# 2s_HY2120-OB.net
KiCad netlist of a schematic drawn in EasyEDA Pro
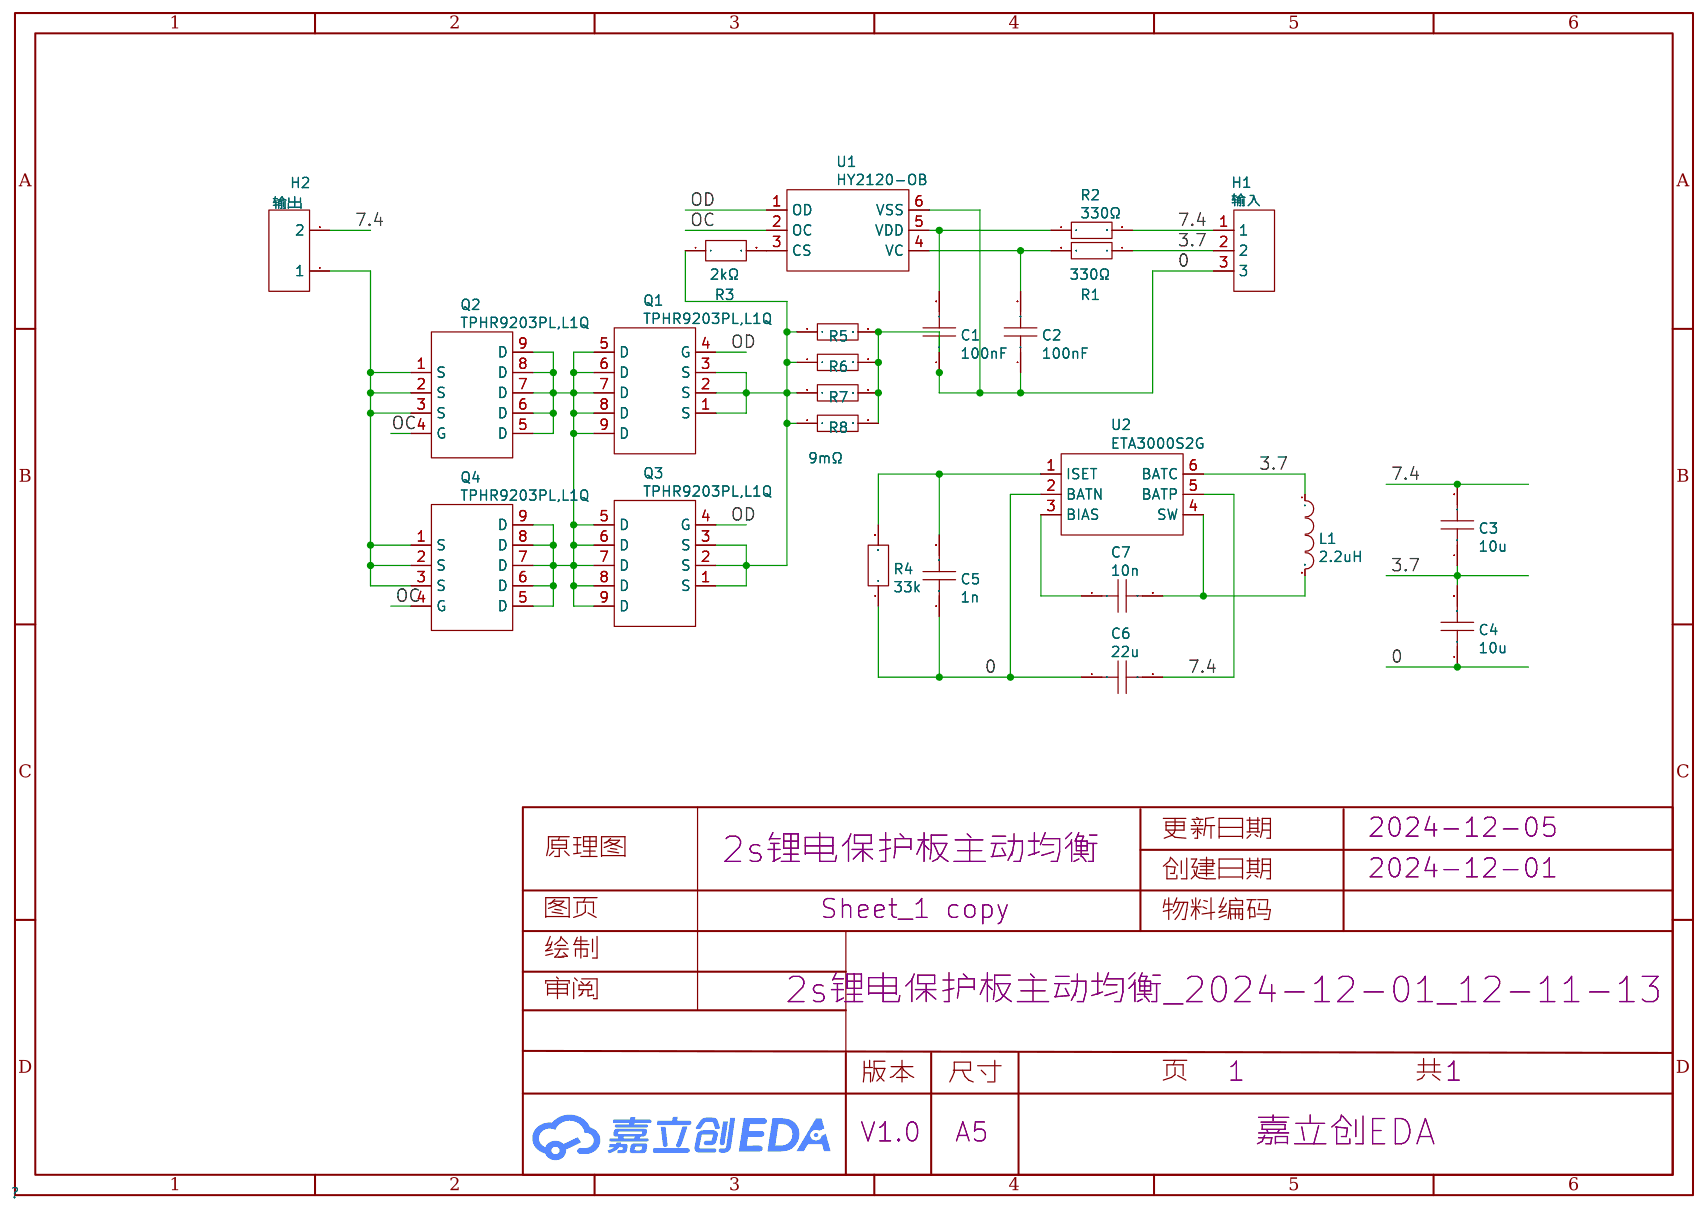
[diagram p0: schematic sheet]

(export (version "E")
  (design (tool "Eeschema 10.0.6"))
  (components
    (comp (ref "C1")
      (value "100nF")
      (footprint "easyedapro:C0603")
      (fields (field (name "Manufacturer Part") "CL10B104KC8NNNC") (field (name "Manufacturer") "SAMSUNG"))
      (libsource (lib "easyedapro") (part "100nF"))
    )
    (comp (ref "C2")
      (value "100nF")
      (footprint "easyedapro:C0603")
      (fields (field (name "Manufacturer Part") "CL10B104KC8NNNC") (field (name "Manufacturer") "SAMSUNG"))
      (libsource (lib "easyedapro") (part "100nF"))
    )
    (comp (ref "C3") (value "10u") (footprint "easyedapro:C0603") (libsource (lib "easyedapro") (part "10u")))
    (comp (ref "C4") (value "10u") (footprint "easyedapro:C0603") (libsource (lib "easyedapro") (part "10u")))
    (comp (ref "C5") (value "1n") (footprint "easyedapro:C0603") (libsource (lib "easyedapro") (part "1n")))
    (comp (ref "C6") (value "22u") (footprint "easyedapro:C0603") (libsource (lib "easyedapro") (part "22u")))
    (comp (ref "C7") (value "10n") (footprint "easyedapro:C0603") (libsource (lib "easyedapro") (part "10n")))
    (comp (ref "H1")
      (value "输入")
      (fields
        (field (name "Manufacturer Part") "Z-211-0311-0021-001")
        (field (name "Manufacturer") "ZHENGLING")
      )
      (libsource (lib "easyedapro") (part "输入"))
    )
    (comp (ref "H2")
      (value "输出")
      (fields (field (name "Manufacturer Part") "826629-2") (field (name "Manufacturer") "TE Connectivity"))
      (libsource (lib "easyedapro") (part "输出"))
    )
    (comp (ref "L1")
      (value "2.2uH")
      (footprint "easyedapro:IND-SMD_L4.4-W4.0_PHC0420")
      (fields (field (name "Manufacturer Part") "PHC0420-2R2M-T") (field (name "Manufacturer") "EMTEK"))
      (libsource (lib "easyedapro") (part "2.2uH"))
    )
    (comp (ref "Q1")
      (value "TPHR9203PL,L1Q")
      (footprint "easyedapro:DSOP-8_L5.0-W5.0-P1.27-EP-TL")
      (fields (field (name "Manufacturer") "TOSHIBA(东芝)"))
      (libsource (lib "easyedapro") (part "TPH1R403NL"))
    )
    (comp (ref "Q2")
      (value "TPHR9203PL,L1Q")
      (footprint "easyedapro:DSOP-8_L5.0-W5.0-P1.27-EP-TL")
      (fields (field (name "Manufacturer") "TOSHIBA(东芝)"))
      (libsource (lib "easyedapro") (part "TPH1R403NL"))
    )
    (comp (ref "Q3")
      (value "TPHR9203PL,L1Q")
      (footprint "easyedapro:DSOP-8_L5.0-W5.0-P1.27-EP-TL")
      (fields (field (name "Manufacturer") "TOSHIBA(东芝)"))
      (libsource (lib "easyedapro") (part "TPH1R403NL"))
    )
    (comp (ref "Q4")
      (value "TPHR9203PL,L1Q")
      (footprint "easyedapro:DSOP-8_L5.0-W5.0-P1.27-EP-TL")
      (fields (field (name "Manufacturer") "TOSHIBA(东芝)"))
      (libsource (lib "easyedapro") (part "TPH1R403NL"))
    )
    (comp (ref "R1")
      (value "330Ω")
      (footprint "easyedapro:R0603")
      (fields
        (field (name "Manufacturer Part") "RN731JTTD3300B25")
        (field (name "Manufacturer") "KOA Speer Elec")
      )
      (libsource (lib "easyedapro") (part "330Ω"))
    )
    (comp (ref "R2")
      (value "330Ω")
      (footprint "easyedapro:R0603")
      (fields
        (field (name "Manufacturer Part") "RN731JTTD3300B25")
        (field (name "Manufacturer") "KOA Speer Elec")
      )
      (libsource (lib "easyedapro") (part "330Ω"))
    )
    (comp (ref "R3")
      (value "2kΩ")
      (footprint "easyedapro:R0603")
      (fields
        (field (name "Manufacturer Part") "0603WAD2001T5E")
        (field (name "Manufacturer") "Uniroyal Elec")
      )
      (libsource (lib "easyedapro") (part "2kΩ"))
    )
    (comp (ref "R4") (value "33k") (footprint "easyedapro:R0603") (libsource (lib "easyedapro") (part "33k")))
    (comp (ref "R5")
      (value "9mΩ")
      (footprint "easyedapro:R1206")
      (description "阻值:9mΩ;精度:±1%;功率:1W;温度系数:±100ppm/°C;")
      (fields
        (field (name "Manufacturer Part") "STE1206M1W0R009F")
        (field (name "Manufacturer") "WALTER(华德)")
      )
      (libsource (lib "easyedapro") (part "STE1206M1W0R009F"))
    )
    (comp (ref "R6")
      (value "9mΩ")
      (footprint "easyedapro:R1206")
      (description "阻值:9mΩ;精度:±1%;功率:1W;温度系数:±100ppm/°C;")
      (fields
        (field (name "Manufacturer Part") "STE1206M1W0R009F")
        (field (name "Manufacturer") "WALTER(华德)")
      )
      (libsource (lib "easyedapro") (part "STE1206M1W0R009F"))
    )
    (comp (ref "R7")
      (value "9mΩ")
      (footprint "easyedapro:R1206")
      (description "阻值:9mΩ;精度:±1%;功率:1W;温度系数:±100ppm/°C;")
      (fields
        (field (name "Manufacturer Part") "STE1206M1W0R009F")
        (field (name "Manufacturer") "WALTER(华德)")
      )
      (libsource (lib "easyedapro") (part "STE1206M1W0R009F"))
    )
    (comp (ref "R8")
      (value "9mΩ")
      (footprint "easyedapro:R1206")
      (description "阻值:9mΩ;精度:±1%;功率:1W;温度系数:±100ppm/°C;")
      (fields
        (field (name "Manufacturer Part") "STE1206M1W0R009F")
        (field (name "Manufacturer") "WALTER(华德)")
      )
      (libsource (lib "easyedapro") (part "STE1206M1W0R009F"))
    )
    (comp (ref "U1")
      (value "HY2120-OB")
      (footprint "easyedapro:SOT-23-6_L2.9-W1.6-P0.95-LS2.8-BR")
      (fields (field (name "Manufacturer Part") "HY2120-LB") (field (name "Manufacturer") "HYCON"))
      (libsource (lib "easyedapro") (part "HY2120-OB"))
    )
    (comp (ref "U2")
      (value "ETA3000S2G")
      (footprint "easyedapro:SOT-23-6_L2.9-W1.6-P0.95-LS2.8-BL")
      (fields (field (name "Manufacturer") "ETA(钰泰)"))
      (libsource (lib "easyedapro") (part "ETA3000S2G"))
    )
  )
  (nets
    (net (code "1") (name "/0") (class "Default")
      (node (ref "C1") (pin "1") (pinfunction "1_1") (pintype "unspecified"))
      (node (ref "C2") (pin "1") (pinfunction "1_1") (pintype "unspecified"))
      (node (ref "C4") (pin "1") (pinfunction "1_1") (pintype "unspecified"))
      (node (ref "C5") (pin "1") (pinfunction "1_1") (pintype "unspecified"))
      (node (ref "C6") (pin "1") (pinfunction "1_1") (pintype "unspecified"))
      (node (ref "H1") (pin "3") (pinfunction "3_3") (pintype "unspecified"))
      (node (ref "R4") (pin "1") (pinfunction "1_1") (pintype "unspecified"))
      (node (ref "R5") (pin "2") (pinfunction "2_2") (pintype "unspecified"))
      (node (ref "R6") (pin "2") (pinfunction "2_2") (pintype "unspecified"))
      (node (ref "R7") (pin "2") (pinfunction "2_2") (pintype "unspecified"))
      (node (ref "R8") (pin "2") (pinfunction "2_2") (pintype "unspecified"))
      (node (ref "U1") (pin "6") (pinfunction "VSS_6") (pintype "unspecified"))
      (node (ref "U2") (pin "2") (pinfunction "BATN_2") (pintype "unspecified"))
    )
    (net (code "2") (name "/3.7") (class "Default")
      (node (ref "C3") (pin "1") (pinfunction "1_1") (pintype "unspecified"))
      (node (ref "C4") (pin "2") (pinfunction "2_2") (pintype "unspecified"))
      (node (ref "H1") (pin "2") (pinfunction "2_2") (pintype "unspecified"))
      (node (ref "L1") (pin "1") (pinfunction "1_1") (pintype "unspecified"))
      (node (ref "R1") (pin "1") (pinfunction "1_1") (pintype "unspecified"))
      (node (ref "U2") (pin "6") (pinfunction "BATC_6") (pintype "unspecified"))
    )
    (net (code "3") (name "/7.4") (class "Default")
      (node (ref "C3") (pin "2") (pinfunction "2_2") (pintype "unspecified"))
      (node (ref "C6") (pin "2") (pinfunction "2_2") (pintype "unspecified"))
      (node (ref "H1") (pin "1") (pinfunction "1_1") (pintype "unspecified"))
      (node (ref "H2") (pin "2") (pinfunction "2_2") (pintype "unspecified"))
      (node (ref "R2") (pin "2") (pinfunction "2_2") (pintype "unspecified"))
      (node (ref "U2") (pin "5") (pinfunction "BATP_5") (pintype "unspecified"))
    )
    (net (code "4") (name "/OC") (class "Default")
      (node (ref "Q2") (pin "4") (pinfunction "G_4") (pintype "unspecified"))
      (node (ref "Q4") (pin "4") (pinfunction "G_4") (pintype "unspecified"))
      (node (ref "U1") (pin "2") (pinfunction "OC_2") (pintype "unspecified"))
    )
    (net (code "5") (name "/OD") (class "Default")
      (node (ref "Q1") (pin "4") (pinfunction "G_4") (pintype "unspecified"))
      (node (ref "Q3") (pin "4") (pinfunction "G_4") (pintype "unspecified"))
      (node (ref "U1") (pin "1") (pinfunction "OD_1") (pintype "unspecified"))
    )
    (net (code "6") (name "Net-(H2-Pad1)") (class "Default")
      (node (ref "H2") (pin "1") (pinfunction "1_1") (pintype "unspecified"))
      (node (ref "Q2") (pin "1") (pinfunction "S_1") (pintype "unspecified"))
      (node (ref "Q2") (pin "2") (pinfunction "S_2") (pintype "unspecified"))
      (node (ref "Q2") (pin "3") (pinfunction "S_3") (pintype "unspecified"))
      (node (ref "Q4") (pin "1") (pinfunction "S_1") (pintype "unspecified"))
      (node (ref "Q4") (pin "2") (pinfunction "S_2") (pintype "unspecified"))
      (node (ref "Q4") (pin "3") (pinfunction "S_3") (pintype "unspecified"))
    )
    (net (code "7") (name "Net-(Q1-D-Pad5)") (class "Default")
      (node (ref "Q1") (pin "5") (pinfunction "D_5") (pintype "unspecified"))
      (node (ref "Q1") (pin "6") (pinfunction "D_6") (pintype "unspecified"))
      (node (ref "Q1") (pin "7") (pinfunction "D_7") (pintype "unspecified"))
      (node (ref "Q1") (pin "8") (pinfunction "D_8") (pintype "unspecified"))
      (node (ref "Q1") (pin "9") (pinfunction "D_9") (pintype "unspecified"))
      (node (ref "Q2") (pin "5") (pinfunction "D_5") (pintype "unspecified"))
      (node (ref "Q2") (pin "6") (pinfunction "D_6") (pintype "unspecified"))
      (node (ref "Q2") (pin "7") (pinfunction "D_7") (pintype "unspecified"))
      (node (ref "Q2") (pin "8") (pinfunction "D_8") (pintype "unspecified"))
      (node (ref "Q2") (pin "9") (pinfunction "D_9") (pintype "unspecified"))
      (node (ref "Q3") (pin "5") (pinfunction "D_5") (pintype "unspecified"))
      (node (ref "Q3") (pin "6") (pinfunction "D_6") (pintype "unspecified"))
      (node (ref "Q3") (pin "7") (pinfunction "D_7") (pintype "unspecified"))
      (node (ref "Q3") (pin "8") (pinfunction "D_8") (pintype "unspecified"))
      (node (ref "Q3") (pin "9") (pinfunction "D_9") (pintype "unspecified"))
      (node (ref "Q4") (pin "5") (pinfunction "D_5") (pintype "unspecified"))
      (node (ref "Q4") (pin "6") (pinfunction "D_6") (pintype "unspecified"))
      (node (ref "Q4") (pin "7") (pinfunction "D_7") (pintype "unspecified"))
      (node (ref "Q4") (pin "8") (pinfunction "D_8") (pintype "unspecified"))
      (node (ref "Q4") (pin "9") (pinfunction "D_9") (pintype "unspecified"))
    )
    (net (code "8") (name "Net-(Q1-S-Pad1)") (class "Default")
      (node (ref "Q1") (pin "1") (pinfunction "S_1") (pintype "unspecified"))
      (node (ref "Q1") (pin "2") (pinfunction "S_2") (pintype "unspecified"))
      (node (ref "Q1") (pin "3") (pinfunction "S_3") (pintype "unspecified"))
      (node (ref "Q3") (pin "1") (pinfunction "S_1") (pintype "unspecified"))
      (node (ref "Q3") (pin "2") (pinfunction "S_2") (pintype "unspecified"))
      (node (ref "Q3") (pin "3") (pinfunction "S_3") (pintype "unspecified"))
      (node (ref "R3") (pin "1") (pinfunction "1_1") (pintype "unspecified"))
      (node (ref "R5") (pin "1") (pinfunction "1_1") (pintype "unspecified"))
      (node (ref "R6") (pin "1") (pinfunction "1_1") (pintype "unspecified"))
      (node (ref "R7") (pin "1") (pinfunction "1_1") (pintype "unspecified"))
      (node (ref "R8") (pin "1") (pinfunction "1_1") (pintype "unspecified"))
    )
    (net (code "9") (name "Net-(U1-CS)") (class "Default")
      (node (ref "R3") (pin "2") (pinfunction "2_2") (pintype "unspecified"))
      (node (ref "U1") (pin "3") (pinfunction "CS_3") (pintype "unspecified"))
    )
    (net (code "10") (name "Net-(U1-VC)") (class "Default")
      (node (ref "C2") (pin "2") (pinfunction "2_2") (pintype "unspecified"))
      (node (ref "R1") (pin "2") (pinfunction "2_2") (pintype "unspecified"))
      (node (ref "U1") (pin "4") (pinfunction "VC_4") (pintype "unspecified"))
    )
    (net (code "11") (name "Net-(U1-VDD)") (class "Default")
      (node (ref "C1") (pin "2") (pinfunction "2_2") (pintype "unspecified"))
      (node (ref "R2") (pin "1") (pinfunction "1_1") (pintype "unspecified"))
      (node (ref "U1") (pin "5") (pinfunction "VDD_5") (pintype "unspecified"))
    )
    (net (code "12") (name "Net-(U2-BIAS)") (class "Default")
      (node (ref "C7") (pin "1") (pinfunction "1_1") (pintype "unspecified"))
      (node (ref "U2") (pin "3") (pinfunction "BIAS_3") (pintype "unspecified"))
    )
    (net (code "13") (name "Net-(U2-ISET)") (class "Default")
      (node (ref "C5") (pin "2") (pinfunction "2_2") (pintype "unspecified"))
      (node (ref "R4") (pin "2") (pinfunction "2_2") (pintype "unspecified"))
      (node (ref "U2") (pin "1") (pinfunction "ISET_1") (pintype "unspecified"))
    )
    (net (code "14") (name "Net-(U2-SW)") (class "Default")
      (node (ref "C7") (pin "2") (pinfunction "2_2") (pintype "unspecified"))
      (node (ref "L1") (pin "2") (pinfunction "2_2") (pintype "unspecified"))
      (node (ref "U2") (pin "4") (pinfunction "SW_4") (pintype "unspecified"))
    )
  )
)
